# main.net
KiCad netlist of a schematic drawn in EAGLE
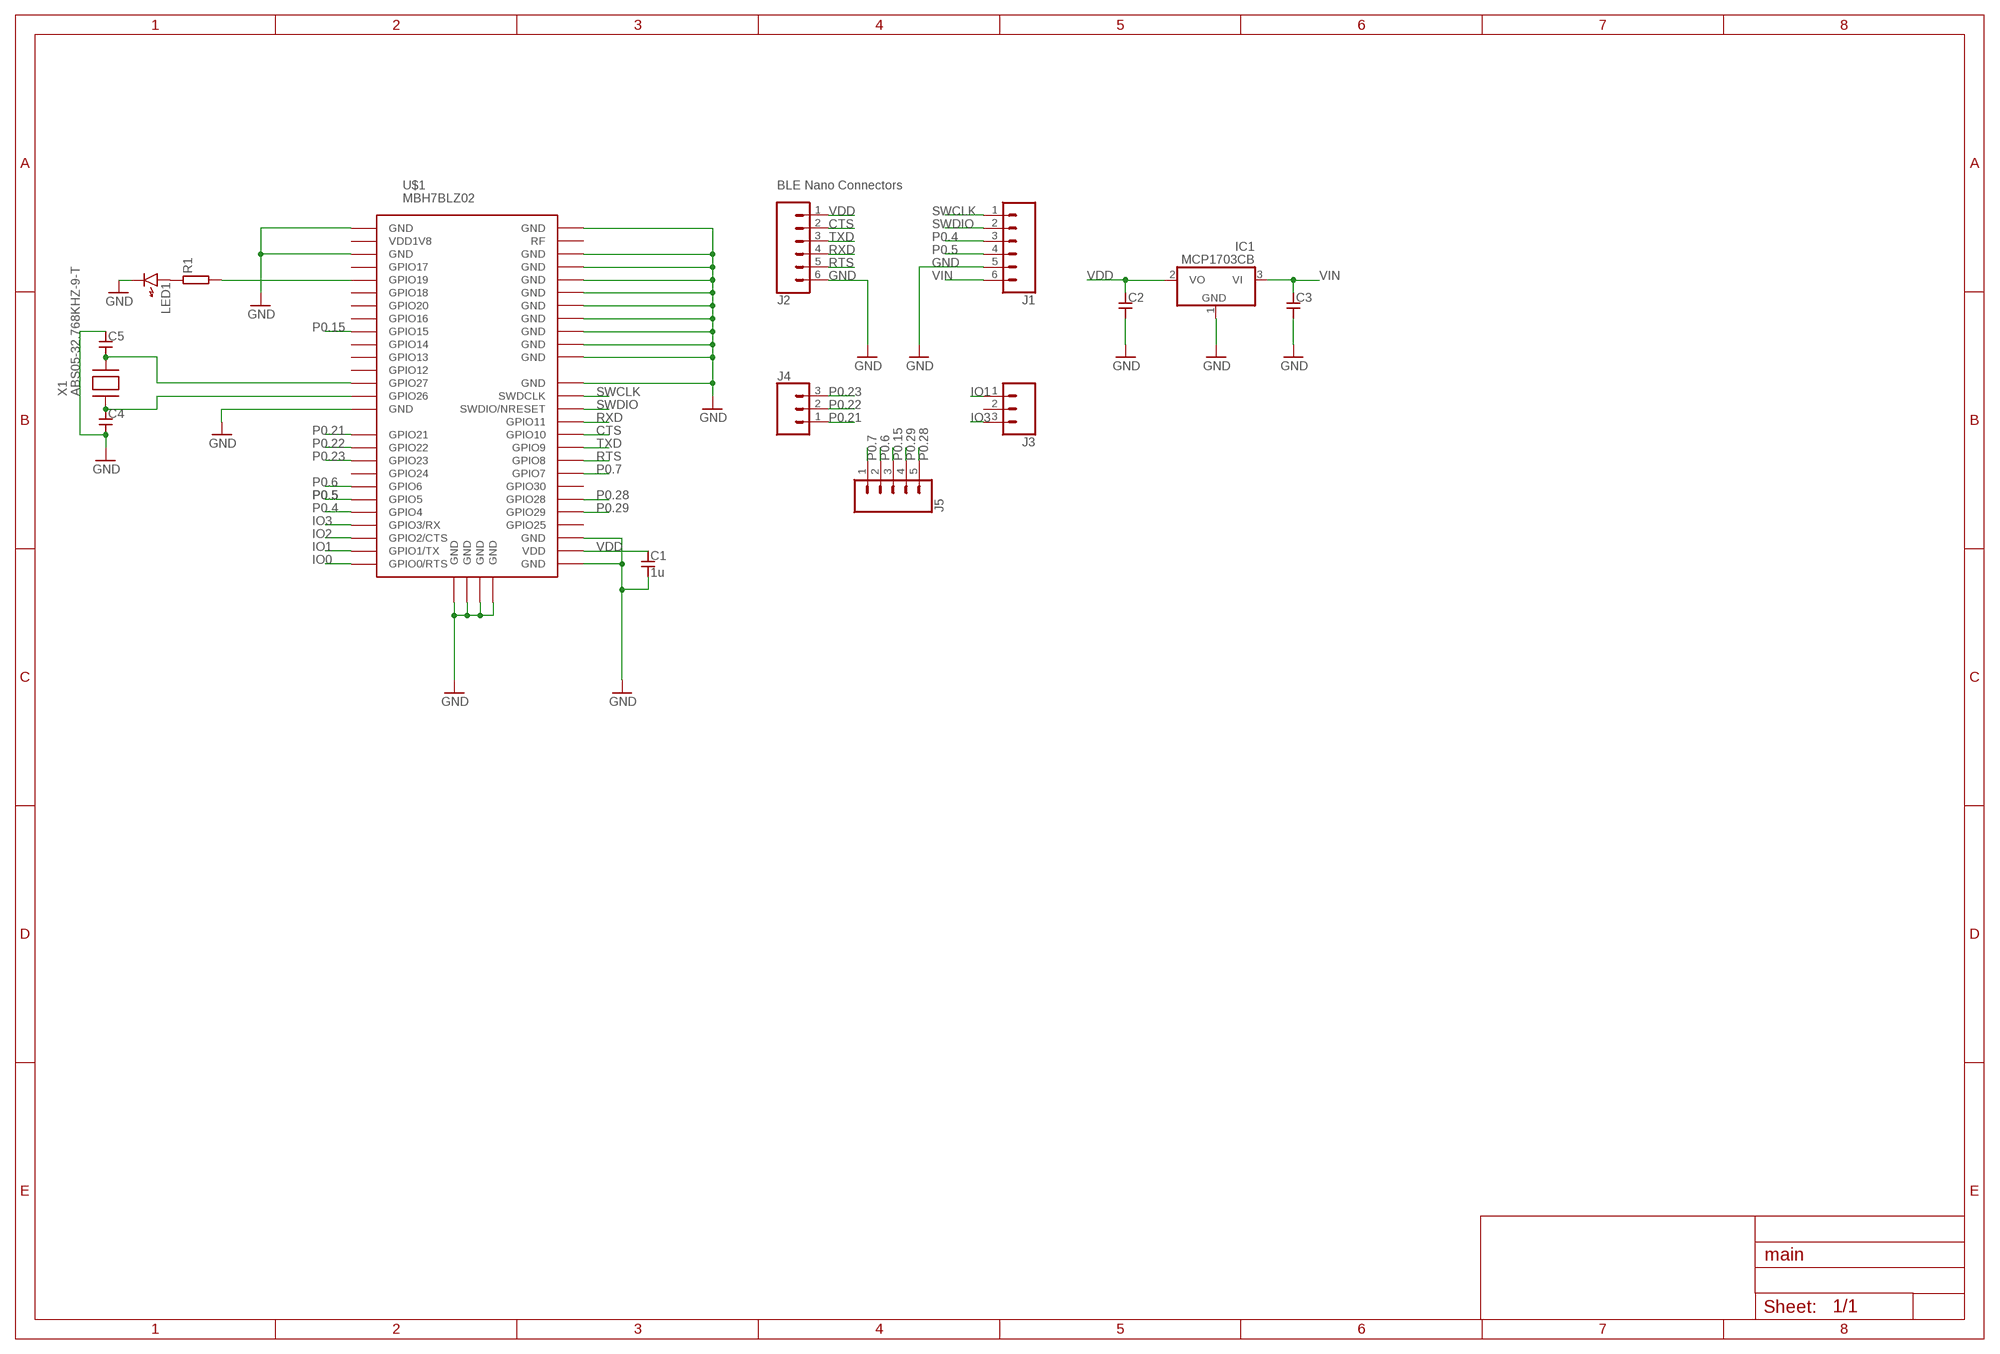
[diagram p0: schematic, sheet 1]

(export (version "E")
  (design (tool "Eeschema 10.0.6"))
  (components
    (comp (ref "C1")
      (value "1u")
      (footprint "eagle-import:SMD1608_REDUCED")
      (libsource (lib "eagle-import") (part "CAPACITOR1608_REDUCED"))
    )
    (comp (ref "C2")
      (value "CAPACITOR1608_REDUCED")
      (footprint "eagle-import:SMD1608_REDUCED")
      (libsource (lib "eagle-import") (part "CAPACITOR1608_REDUCED"))
    )
    (comp (ref "C3")
      (value "CAPACITOR1608_REDUCED")
      (footprint "eagle-import:SMD1608_REDUCED")
      (libsource (lib "eagle-import") (part "CAPACITOR1608_REDUCED"))
    )
    (comp (ref "C4")
      (value "CAPACITOR1005")
      (footprint "eagle-import:SMD1005")
      (libsource (lib "eagle-import") (part "CAPACITOR1005"))
    )
    (comp (ref "C5")
      (value "CAPACITOR1005")
      (footprint "eagle-import:SMD1005")
      (libsource (lib "eagle-import") (part "CAPACITOR1005"))
    )
    (comp (ref "IC1")
      (value "MCP1703CB")
      (footprint "eagle-import:SOT23")
      (libsource (lib "eagle-import") (part "MCP1703CB"))
    )
    (comp (ref "J1")
      (value "CONN_06NO_SILK_FEMALE_PTH")
      (footprint "eagle-import:1X06_NO_SILK")
      (libsource (lib "eagle-import") (part "CONN_06NO_SILK_FEMALE_PTH"))
    )
    (comp (ref "J2")
      (value "CONN_06NO_SILK_FEMALE_PTH")
      (footprint "eagle-import:1X06_NO_SILK")
      (libsource (lib "eagle-import") (part "CONN_06NO_SILK_FEMALE_PTH"))
    )
    (comp (ref "J3")
      (value "CONN_031X03_NO_SILK")
      (footprint "eagle-import:1X03_NO_SILK")
      (libsource (lib "eagle-import") (part "CONN_031X03_NO_SILK"))
    )
    (comp (ref "J4")
      (value "CONN_031X03_NO_SILK")
      (footprint "eagle-import:1X03_NO_SILK")
      (libsource (lib "eagle-import") (part "CONN_031X03_NO_SILK"))
    )
    (comp (ref "J5")
      (value "CONN_05NO_SILK")
      (footprint "eagle-import:1X05_NO_SILK")
      (libsource (lib "eagle-import") (part "CONN_05NO_SILK"))
    )
    (comp (ref "LED1")
      (value "LED1608_REDUCED")
      (footprint "eagle-import:LED1608_REDUCED")
      (libsource (lib "eagle-import") (part "LED1608_REDUCED"))
    )
    (comp (ref "R1")
      (value "RESISTOR1005")
      (footprint "eagle-import:SMD1005")
      (libsource (lib "eagle-import") (part "RESISTOR1005"))
    )
    (comp (ref "U$1")
      (value "MBH7BLZ02")
      (footprint "eagle-import:MBH7BLZ02")
      (libsource (lib "eagle-import") (part "MBH7BLZ02"))
    )
    (comp (ref "X1")
      (value "ABS05-32.768KHZ-9-T")
      (footprint "eagle-import:SMD1610")
      (libsource (lib "eagle-import") (part "ABS05-32.768KHZ-9-T"))
    )
  )
  (nets
    (net (code "1") (name "/CTS") (class "Default")
      (node (ref "J2") (pin "2") (pinfunction "2_2") (pintype "passive"))
      (node (ref "U$1") (pin "P$37") (pinfunction "GPIO10_P$37") (pintype "bidirectional"))
    )
    (net (code "2") (name "/IO0") (class "Default")
      (node (ref "U$1") (pin "P$26") (pinfunction "GPIO0/RTS_P$26") (pintype "bidirectional"))
    )
    (net (code "3") (name "/IO1") (class "Default")
      (node (ref "J3") (pin "1") (pinfunction "1_1") (pintype "passive"))
      (node (ref "U$1") (pin "P$25") (pinfunction "GPIO1/TX_P$25") (pintype "bidirectional"))
    )
    (net (code "4") (name "/IO2") (class "Default")
      (node (ref "U$1") (pin "P$24") (pinfunction "GPIO2/CTS_P$24") (pintype "bidirectional"))
    )
    (net (code "5") (name "/IO3") (class "Default")
      (node (ref "J3") (pin "3") (pinfunction "3_3") (pintype "passive"))
      (node (ref "U$1") (pin "P$23") (pinfunction "GPIO3/RX_P$23") (pintype "bidirectional"))
    )
    (net (code "6") (name "/P0.4") (class "Default")
      (node (ref "J1") (pin "3") (pinfunction "3_3") (pintype "passive"))
      (node (ref "U$1") (pin "P$22") (pinfunction "GPIO4_P$22") (pintype "bidirectional"))
    )
    (net (code "7") (name "/P0.5") (class "Default")
      (node (ref "J1") (pin "4") (pinfunction "4_4") (pintype "passive"))
      (node (ref "U$1") (pin "P$21") (pinfunction "GPIO5_P$21") (pintype "bidirectional"))
    )
    (net (code "8") (name "/P0.6") (class "Default")
      (node (ref "J5") (pin "2") (pinfunction "2_2") (pintype "passive"))
      (node (ref "U$1") (pin "P$20") (pinfunction "GPIO6_P$20") (pintype "bidirectional"))
    )
    (net (code "9") (name "/P0.7") (class "Default")
      (node (ref "J5") (pin "1") (pinfunction "1_1") (pintype "passive"))
      (node (ref "U$1") (pin "P$34") (pinfunction "GPIO7_P$34") (pintype "bidirectional"))
    )
    (net (code "10") (name "/P0.15") (class "Default")
      (node (ref "J5") (pin "3") (pinfunction "3_3") (pintype "passive"))
      (node (ref "U$1") (pin "P$9") (pinfunction "GPIO15_P$9") (pintype "bidirectional"))
    )
    (net (code "11") (name "/P0.21") (class "Default")
      (node (ref "J4") (pin "1") (pinfunction "1_1") (pintype "passive"))
      (node (ref "U$1") (pin "P$16") (pinfunction "GPIO21_P$16") (pintype "bidirectional"))
    )
    (net (code "12") (name "/P0.22") (class "Default")
      (node (ref "J4") (pin "2") (pinfunction "2_2") (pintype "passive"))
      (node (ref "U$1") (pin "P$17") (pinfunction "GPIO22_P$17") (pintype "bidirectional"))
    )
    (net (code "13") (name "/P0.23") (class "Default")
      (node (ref "J4") (pin "3") (pinfunction "3_3") (pintype "passive"))
      (node (ref "U$1") (pin "P$18") (pinfunction "GPIO23_P$18") (pintype "bidirectional"))
    )
    (net (code "14") (name "/P0.28") (class "Default")
      (node (ref "J5") (pin "5") (pinfunction "5_5") (pintype "passive"))
      (node (ref "U$1") (pin "P$32") (pinfunction "GPIO28_P$32") (pintype "bidirectional"))
    )
    (net (code "15") (name "/P0.29") (class "Default")
      (node (ref "J5") (pin "4") (pinfunction "4_4") (pintype "passive"))
      (node (ref "U$1") (pin "P$31") (pinfunction "GPIO29_P$31") (pintype "bidirectional"))
    )
    (net (code "16") (name "/RTS") (class "Default")
      (node (ref "J2") (pin "5") (pinfunction "5_5") (pintype "passive"))
      (node (ref "U$1") (pin "P$35") (pinfunction "GPIO8_P$35") (pintype "bidirectional"))
    )
    (net (code "17") (name "/RXD") (class "Default")
      (node (ref "J2") (pin "4") (pinfunction "4_4") (pintype "passive"))
      (node (ref "U$1") (pin "P$38") (pinfunction "GPIO11_P$38") (pintype "bidirectional"))
    )
    (net (code "18") (name "/SWCLK") (class "Default")
      (node (ref "J1") (pin "1") (pinfunction "1_1") (pintype "passive"))
      (node (ref "U$1") (pin "P$40") (pinfunction "SWDCLK_P$40") (pintype "bidirectional"))
    )
    (net (code "19") (name "/SWDIO") (class "Default")
      (node (ref "J1") (pin "2") (pinfunction "2_2") (pintype "passive"))
      (node (ref "U$1") (pin "P$39") (pinfunction "SWDIO/NRESET_P$39") (pintype "bidirectional"))
    )
    (net (code "20") (name "/TXD") (class "Default")
      (node (ref "J2") (pin "3") (pinfunction "3_3") (pintype "passive"))
      (node (ref "U$1") (pin "P$36") (pinfunction "GPIO9_P$36") (pintype "bidirectional"))
    )
    (net (code "21") (name "/VDD") (class "Default")
      (node (ref "C1") (pin "1") (pinfunction "1_1") (pintype "passive"))
      (node (ref "C2") (pin "1") (pinfunction "1_1") (pintype "passive"))
      (node (ref "IC1") (pin "2") (pinfunction "VO_2") (pintype "passive"))
      (node (ref "J2") (pin "1") (pinfunction "1_1") (pintype "passive"))
      (node (ref "U$1") (pin "P$28") (pinfunction "VDD_P$28") (pintype "bidirectional"))
    )
    (net (code "22") (name "/VIN") (class "Default")
      (node (ref "C3") (pin "1") (pinfunction "1_1") (pintype "passive"))
      (node (ref "IC1") (pin "3") (pinfunction "VI_3") (pintype "input"))
      (node (ref "J1") (pin "6") (pinfunction "6_6") (pintype "passive"))
    )
    (net (code "23") (name "GND") (class "Default")
      (node (ref "C1") (pin "2") (pinfunction "2_2") (pintype "passive"))
      (node (ref "C2") (pin "2") (pinfunction "2_2") (pintype "passive"))
      (node (ref "C3") (pin "2") (pinfunction "2_2") (pintype "passive"))
      (node (ref "C4") (pin "2") (pinfunction "2_2") (pintype "passive"))
      (node (ref "C5") (pin "1") (pinfunction "1_1") (pintype "passive"))
      (node (ref "IC1") (pin "1") (pinfunction "GND_1") (pintype "passive"))
      (node (ref "J1") (pin "5") (pinfunction "5_5") (pintype "passive"))
      (node (ref "J2") (pin "6") (pinfunction "6_6") (pintype "passive"))
      (node (ref "LED1") (pin "K") (pinfunction "K_K") (pintype "passive"))
      (node (ref "U$1") (pin "P$1") (pinfunction "GND_P$1") (pintype "bidirectional"))
      (node (ref "U$1") (pin "P$15") (pinfunction "GND_P$15") (pintype "bidirectional"))
      (node (ref "U$1") (pin "P$27") (pinfunction "GND_P$27") (pintype "bidirectional"))
      (node (ref "U$1") (pin "P$29") (pinfunction "GND_P$29") (pintype "bidirectional"))
      (node (ref "U$1") (pin "P$3") (pinfunction "GND_P$3") (pintype "bidirectional"))
      (node (ref "U$1") (pin "P$41") (pinfunction "GND_P$41") (pintype "bidirectional"))
      (node (ref "U$1") (pin "P$42") (pinfunction "GND_P$42") (pintype "bidirectional"))
      (node (ref "U$1") (pin "P$43") (pinfunction "GND_P$43") (pintype "bidirectional"))
      (node (ref "U$1") (pin "P$44") (pinfunction "GND_P$44") (pintype "bidirectional"))
      (node (ref "U$1") (pin "P$45") (pinfunction "GND_P$45") (pintype "bidirectional"))
      (node (ref "U$1") (pin "P$46") (pinfunction "GND_P$46") (pintype "bidirectional"))
      (node (ref "U$1") (pin "P$47") (pinfunction "GND_P$47") (pintype "bidirectional"))
      (node (ref "U$1") (pin "P$48") (pinfunction "GND_P$48") (pintype "bidirectional"))
      (node (ref "U$1") (pin "P$49") (pinfunction "GND_P$49") (pintype "bidirectional"))
      (node (ref "U$1") (pin "P$50") (pinfunction "GND_P$50") (pintype "bidirectional"))
      (node (ref "U$1") (pin "P$52") (pinfunction "GND_P$52") (pintype "bidirectional"))
      (node (ref "U$1") (pin "P$53") (pinfunction "GND_P$53") (pintype "bidirectional"))
      (node (ref "U$1") (pin "P$54") (pinfunction "GND_P$54") (pintype "bidirectional"))
      (node (ref "U$1") (pin "P$55") (pinfunction "GND_P$55") (pintype "bidirectional"))
      (node (ref "U$1") (pin "P$56") (pinfunction "GND_P$56") (pintype "bidirectional"))
    )
    (net (code "24") (name "Net-(LED1-PadA)") (class "Default")
      (node (ref "LED1") (pin "A") (pinfunction "A_A") (pintype "passive"))
      (node (ref "R1") (pin "1") (pinfunction "1_1") (pintype "passive"))
    )
    (net (code "25") (name "Net-(U$1-GPIO19)") (class "Default")
      (node (ref "R1") (pin "2") (pinfunction "2_2") (pintype "passive"))
      (node (ref "U$1") (pin "P$5") (pinfunction "GPIO19_P$5") (pintype "bidirectional"))
    )
    (net (code "26") (name "Net-(U$1-GPIO26)") (class "Default")
      (node (ref "C4") (pin "1") (pinfunction "1_1") (pintype "passive"))
      (node (ref "U$1") (pin "P$14") (pinfunction "GPIO26_P$14") (pintype "bidirectional"))
      (node (ref "X1") (pin "1") (pinfunction "1_1") (pintype "bidirectional"))
    )
    (net (code "27") (name "Net-(U$1-GPIO27)") (class "Default")
      (node (ref "C5") (pin "2") (pinfunction "2_2") (pintype "passive"))
      (node (ref "U$1") (pin "P$13") (pinfunction "GPIO27_P$13") (pintype "bidirectional"))
      (node (ref "X1") (pin "2") (pinfunction "2_2") (pintype "bidirectional"))
    )
    (net (code "28") (name "unconnected-(J3-Pad2)") (class "Default")
      (node (ref "J3") (pin "2") (pinfunction "2_2") (pintype "passive"))
    )
    (net (code "29") (name "unconnected-(U$1-GPIO12-PadP$12)") (class "Default")
      (node (ref "U$1") (pin "P$12") (pinfunction "GPIO12_P$12") (pintype "bidirectional"))
    )
    (net (code "30") (name "unconnected-(U$1-GPIO13-PadP$11)") (class "Default")
      (node (ref "U$1") (pin "P$11") (pinfunction "GPIO13_P$11") (pintype "bidirectional"))
    )
    (net (code "31") (name "unconnected-(U$1-GPIO14-PadP$10)") (class "Default")
      (node (ref "U$1") (pin "P$10") (pinfunction "GPIO14_P$10") (pintype "bidirectional"))
    )
    (net (code "32") (name "unconnected-(U$1-GPIO16-PadP$8)") (class "Default")
      (node (ref "U$1") (pin "P$8") (pinfunction "GPIO16_P$8") (pintype "bidirectional"))
    )
    (net (code "33") (name "unconnected-(U$1-GPIO17-PadP$4)") (class "Default")
      (node (ref "U$1") (pin "P$4") (pinfunction "GPIO17_P$4") (pintype "bidirectional"))
    )
    (net (code "34") (name "unconnected-(U$1-GPIO18-PadP$6)") (class "Default")
      (node (ref "U$1") (pin "P$6") (pinfunction "GPIO18_P$6") (pintype "bidirectional"))
    )
    (net (code "35") (name "unconnected-(U$1-GPIO20-PadP$7)") (class "Default")
      (node (ref "U$1") (pin "P$7") (pinfunction "GPIO20_P$7") (pintype "bidirectional"))
    )
    (net (code "36") (name "unconnected-(U$1-GPIO24-PadP$19)") (class "Default")
      (node (ref "U$1") (pin "P$19") (pinfunction "GPIO24_P$19") (pintype "bidirectional"))
    )
    (net (code "37") (name "unconnected-(U$1-GPIO25-PadP$30)") (class "Default")
      (node (ref "U$1") (pin "P$30") (pinfunction "GPIO25_P$30") (pintype "bidirectional"))
    )
    (net (code "38") (name "unconnected-(U$1-GPIO30-PadP$33)") (class "Default")
      (node (ref "U$1") (pin "P$33") (pinfunction "GPIO30_P$33") (pintype "bidirectional"))
    )
    (net (code "39") (name "unconnected-(U$1-RF-PadP$51)") (class "Default")
      (node (ref "U$1") (pin "P$51") (pinfunction "RF_P$51") (pintype "bidirectional"))
    )
    (net (code "40") (name "unconnected-(U$1-VDD1V8-PadP$2)") (class "Default")
      (node (ref "U$1") (pin "P$2") (pinfunction "VDD1V8_P$2") (pintype "bidirectional"))
    )
  )
)
